# USB.net
KiCad netlist of a schematic drawn in Altium Designer
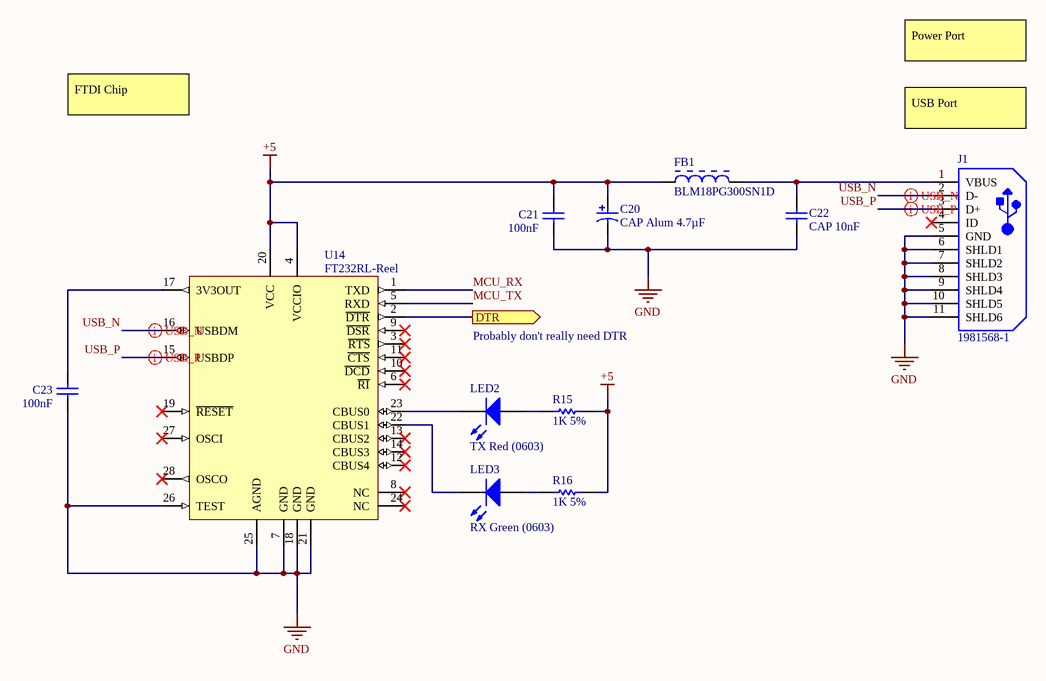
[diagram p0: USB.SchDoc]

(export (version "E")
  (design (tool "Eeschema 10.0.6"))
  (components
    (comp (ref "C20")
      (value "CAP Alum 4.7µF")
      (footprint "NIC-CAPA2-4X5.8_V")
      (fields (field (name "MANUFACTURER") "Nichicon") (field (name "PARTNUMBER") "UUD1V4R7MCL1GS"))
      (libsource (lib "Altium Content Vault") (part "NIC-CAP-P-2"))
    )
    (comp (ref "C21")
      (value "100nF")
      (footprint "CAPC0603(1608)100_M")
      (description "CAP 100nF 16V ±5% 0603 (1608 Metric) Thickness 1mm SMD")
      (fields (field (name "TOLERANCE") "Â±5%"))
      (libsource (lib "Altium Content Vault") (part "CAP"))
    )
    (comp (ref "C22")
      (value "CAP 10nF")
      (footprint "CAPC0603(1608)100_M")
      (description "CAP 10nF 10V ±10% 0603 (1608 Metric) Thickness 1mm SMD")
      (fields (field (name "TOLERANCE") "Â±10%"))
      (libsource (lib "Altium Content Vault") (part "CAP"))
    )
    (comp (ref "C23")
      (value "100nF")
      (footprint "CAPC0603(1608)100_M")
      (description "CAP 100nF 16V ±5% 0603 (1608 Metric) Thickness 1mm SMD")
      (fields (field (name "TOLERANCE") "Â±5%"))
      (libsource (lib "Altium Content Vault") (part "CAP"))
    )
    (comp (ref "FB1")
      (value "BLM18PG300SN1D")
      (footprint "MURA-BLM18PG_KG-CHIP-2_V1")
      (fields (field (name "MANUFACTURER") "Murata"))
      (libsource (lib "Altium Content Vault") (part "MURA-FB-2"))
    )
    (comp (ref "J1")
      (value "1981568-1")
      (footprint "TECO-1981568-5_V")
      (description "Micro USB Receptacle Standard Type B Assy, 5-Pin SMD, RoHS, Tape and Reel")
      (fields (field (name "MANUFACTURER") "TE Connectivity"))
      (libsource (lib "Altium Content Vault") (part "USB-5-6SHLD"))
    )
    (comp (ref "LED2")
      (value "TX Red (0603)")
      (footprint "0603_A")
      (description "SMD mono-color Chip LED, WL-SMCW, Red")
      (fields (field (name "MANUFACTURER") "Wuerth Elektronik") (field (name "PARTNUMBER") "150060RS75000"))
      (libsource (lib "Altium Content Vault") (part "WE-LED_K1A2-2"))
    )
    (comp (ref "LED3")
      (value "RX Green (0603)")
      (footprint "LITE-ON-LTST-C191KRKT-2_V")
      (description "Chip LED, Green, 574 nm, 40 pF, -55 to 85 degC, 2-Pin SMD, RoHS, Tape and Reel")
      (fields (field (name "MANUFACTURER") "Lite-On"))
      (libsource (lib "Altium Content Vault") (part "LED-AK-2"))
    )
    (comp (ref "R15")
      (value "1K 5%")
      (footprint "RESC0603(1608)_L")
      (description "1K 0.1W 5% 0603 (1608 Metric)  SMD")
      (fields (field (name "TOLERANCE") "5 %") (field (name "POWER") "0.1 W"))
      (libsource (lib "Altium Content Vault") (part "RES"))
    )
    (comp (ref "R16")
      (value "1K 5%")
      (footprint "RESC0603(1608)_L")
      (description "1K 0.1W 5% 0603 (1608 Metric)  SMD")
      (fields (field (name "TOLERANCE") "5 %") (field (name "POWER") "0.1 W"))
      (libsource (lib "Altium Content Vault") (part "RES"))
    )
    (comp (ref "U14")
      (value "FT232RL-Reel")
      (footprint "SSOP-28_L")
      (description "USB UART Asynchronous Serial Data Transfer Chip, 28-pin SSOP, Tape and Reel")
      (fields (field (name "MANUFACTURER") "FTDI"))
      (libsource (lib "Altium Content Vault") (part "COM-UART-FT232R-IL28"))
    )
  )
  (nets
    (net (code "1") (name "+5") (class "Default")
      (node (ref "C20") (pin "1") (pinfunction "1_1") (pintype "passive"))
      (node (ref "C21") (pin "2") (pinfunction "2_2") (pintype "passive"))
      (node (ref "FB1") (pin "1") (pinfunction "1_1") (pintype "passive"))
      (node (ref "R15") (pin "1") (pinfunction "1_1") (pintype "passive"))
      (node (ref "R16") (pin "1") (pinfunction "1_1") (pintype "passive"))
      (node (ref "U14") (pin "20") (pinfunction "VCC_20") (pintype "power_in"))
      (node (ref "U14") (pin "4") (pinfunction "VCCIO_4") (pintype "power_in"))
    )
    (net (code "2") (name "/DTR") (class "Default")
      (node (ref "U14") (pin "2") (pinfunction "~{DTR}_2") (pintype "output"))
    )
    (net (code "3") (name "/MCU_RX") (class "Default")
      (node (ref "U14") (pin "1") (pinfunction "TXD_1") (pintype "output"))
    )
    (net (code "4") (name "/MCU_TX") (class "Default")
      (node (ref "U14") (pin "5") (pinfunction "RXD_5") (pintype "input"))
    )
    (net (code "5") (name "/USB_N") (class "Default")
      (node (ref "J1") (pin "2") (pinfunction "D-_2") (pintype "passive"))
      (node (ref "U14") (pin "16") (pinfunction "USBDM_16") (pintype "bidirectional"))
    )
    (net (code "6") (name "/USB_P") (class "Default")
      (node (ref "J1") (pin "3") (pinfunction "D+_3") (pintype "passive"))
      (node (ref "U14") (pin "15") (pinfunction "USBDP_15") (pintype "bidirectional"))
    )
    (net (code "7") (name "GND") (class "Default")
      (node (ref "C20") (pin "2") (pinfunction "2_2") (pintype "passive"))
      (node (ref "C21") (pin "1") (pinfunction "1_1") (pintype "passive"))
      (node (ref "C22") (pin "1") (pinfunction "1_1") (pintype "passive"))
      (node (ref "C23") (pin "1") (pinfunction "1_1") (pintype "passive"))
      (node (ref "J1") (pin "10") (pinfunction "SHLD5_10") (pintype "passive"))
      (node (ref "J1") (pin "11") (pinfunction "SHLD6_11") (pintype "passive"))
      (node (ref "J1") (pin "5") (pinfunction "GND_5") (pintype "passive"))
      (node (ref "J1") (pin "6") (pinfunction "SHLD1_6") (pintype "passive"))
      (node (ref "J1") (pin "7") (pinfunction "SHLD2_7") (pintype "passive"))
      (node (ref "J1") (pin "8") (pinfunction "SHLD3_8") (pintype "passive"))
      (node (ref "J1") (pin "9") (pinfunction "SHLD4_9") (pintype "passive"))
      (node (ref "U14") (pin "18") (pinfunction "GND_18") (pintype "power_in"))
      (node (ref "U14") (pin "21") (pinfunction "GND_21") (pintype "power_in"))
      (node (ref "U14") (pin "25") (pinfunction "AGND_25") (pintype "power_in"))
      (node (ref "U14") (pin "26") (pinfunction "TEST_26") (pintype "input"))
      (node (ref "U14") (pin "7") (pinfunction "GND_7") (pintype "power_in"))
    )
    (net (code "8") (name "Net-(J1-VBUS)") (class "Default")
      (node (ref "C22") (pin "2") (pinfunction "2_2") (pintype "passive"))
      (node (ref "FB1") (pin "2") (pinfunction "2_2") (pintype "passive"))
      (node (ref "J1") (pin "1") (pinfunction "VBUS_1") (pintype "passive"))
    )
    (net (code "9") (name "Net-(LED2-A)") (class "Default")
      (node (ref "LED2") (pin "2") (pinfunction "A_2") (pintype "passive"))
      (node (ref "R15") (pin "2") (pinfunction "2_2") (pintype "passive"))
    )
    (net (code "10") (name "Net-(LED2-K)") (class "Default")
      (node (ref "LED2") (pin "1") (pinfunction "K_1") (pintype "passive"))
      (node (ref "U14") (pin "23") (pinfunction "CBUS0_23") (pintype "bidirectional"))
    )
    (net (code "11") (name "Net-(LED3-A)") (class "Default")
      (node (ref "LED3") (pin "1") (pinfunction "A_1") (pintype "passive"))
      (node (ref "R16") (pin "2") (pinfunction "2_2") (pintype "passive"))
    )
    (net (code "12") (name "Net-(LED3-K)") (class "Default")
      (node (ref "LED3") (pin "2") (pinfunction "K_2") (pintype "passive"))
      (node (ref "U14") (pin "22") (pinfunction "CBUS1_22") (pintype "bidirectional"))
    )
    (net (code "13") (name "Net-(U14-3V3OUT)") (class "Default")
      (node (ref "C23") (pin "2") (pinfunction "2_2") (pintype "passive"))
      (node (ref "U14") (pin "17") (pinfunction "3V3OUT_17") (pintype "output"))
    )
    (net (code "14") (name "unconnected-(J1-ID-Pad4)") (class "Default")
      (node (ref "J1") (pin "4") (pinfunction "ID_4") (pintype "passive+no_connect"))
    )
    (net (code "15") (name "unconnected-(U14-CBUS2-Pad13)") (class "Default")
      (node (ref "U14") (pin "13") (pinfunction "CBUS2_13") (pintype "bidirectional+no_connect"))
    )
    (net (code "16") (name "unconnected-(U14-CBUS3-Pad14)") (class "Default")
      (node (ref "U14") (pin "14") (pinfunction "CBUS3_14") (pintype "bidirectional+no_connect"))
    )
    (net (code "17") (name "unconnected-(U14-CBUS4-Pad12)") (class "Default")
      (node (ref "U14") (pin "12") (pinfunction "CBUS4_12") (pintype "bidirectional+no_connect"))
    )
    (net (code "18") (name "unconnected-(U14-NC-Pad8)") (class "Default")
      (node (ref "U14") (pin "8") (pinfunction "NC_8") (pintype "passive+no_connect"))
    )
    (net (code "19") (name "unconnected-(U14-NC-Pad24)") (class "Default")
      (node (ref "U14") (pin "24") (pinfunction "NC_24") (pintype "passive+no_connect"))
    )
    (net (code "20") (name "unconnected-(U14-OSCI-Pad27)") (class "Default")
      (node (ref "U14") (pin "27") (pinfunction "OSCI_27") (pintype "input+no_connect"))
    )
    (net (code "21") (name "unconnected-(U14-OSCO-Pad28)") (class "Default")
      (node (ref "U14") (pin "28") (pinfunction "OSCO_28") (pintype "output+no_connect"))
    )
    (net (code "22") (name "unconnected-(U14-~{CTS}-Pad11)") (class "Default")
      (node (ref "U14") (pin "11") (pinfunction "~{CTS}_11") (pintype "input+no_connect"))
    )
    (net (code "23") (name "unconnected-(U14-~{DCD}-Pad10)") (class "Default")
      (node (ref "U14") (pin "10") (pinfunction "~{DCD}_10") (pintype "input+no_connect"))
    )
    (net (code "24") (name "unconnected-(U14-~{DSR}-Pad9)") (class "Default")
      (node (ref "U14") (pin "9") (pinfunction "~{DSR}_9") (pintype "input+no_connect"))
    )
    (net (code "25") (name "unconnected-(U14-~{RESET}-Pad19)") (class "Default")
      (node (ref "U14") (pin "19") (pinfunction "~{RESET}_19") (pintype "input+no_connect"))
    )
    (net (code "26") (name "unconnected-(U14-~{RI}-Pad6)") (class "Default")
      (node (ref "U14") (pin "6") (pinfunction "~{RI}_6") (pintype "input+no_connect"))
    )
    (net (code "27") (name "unconnected-(U14-~{RTS}-Pad3)") (class "Default")
      (node (ref "U14") (pin "3") (pinfunction "~{RTS}_3") (pintype "output+no_connect"))
    )
  )
)
